# MBC3_1-4.net
KiCad netlist of a schematic drawn in EAGLE
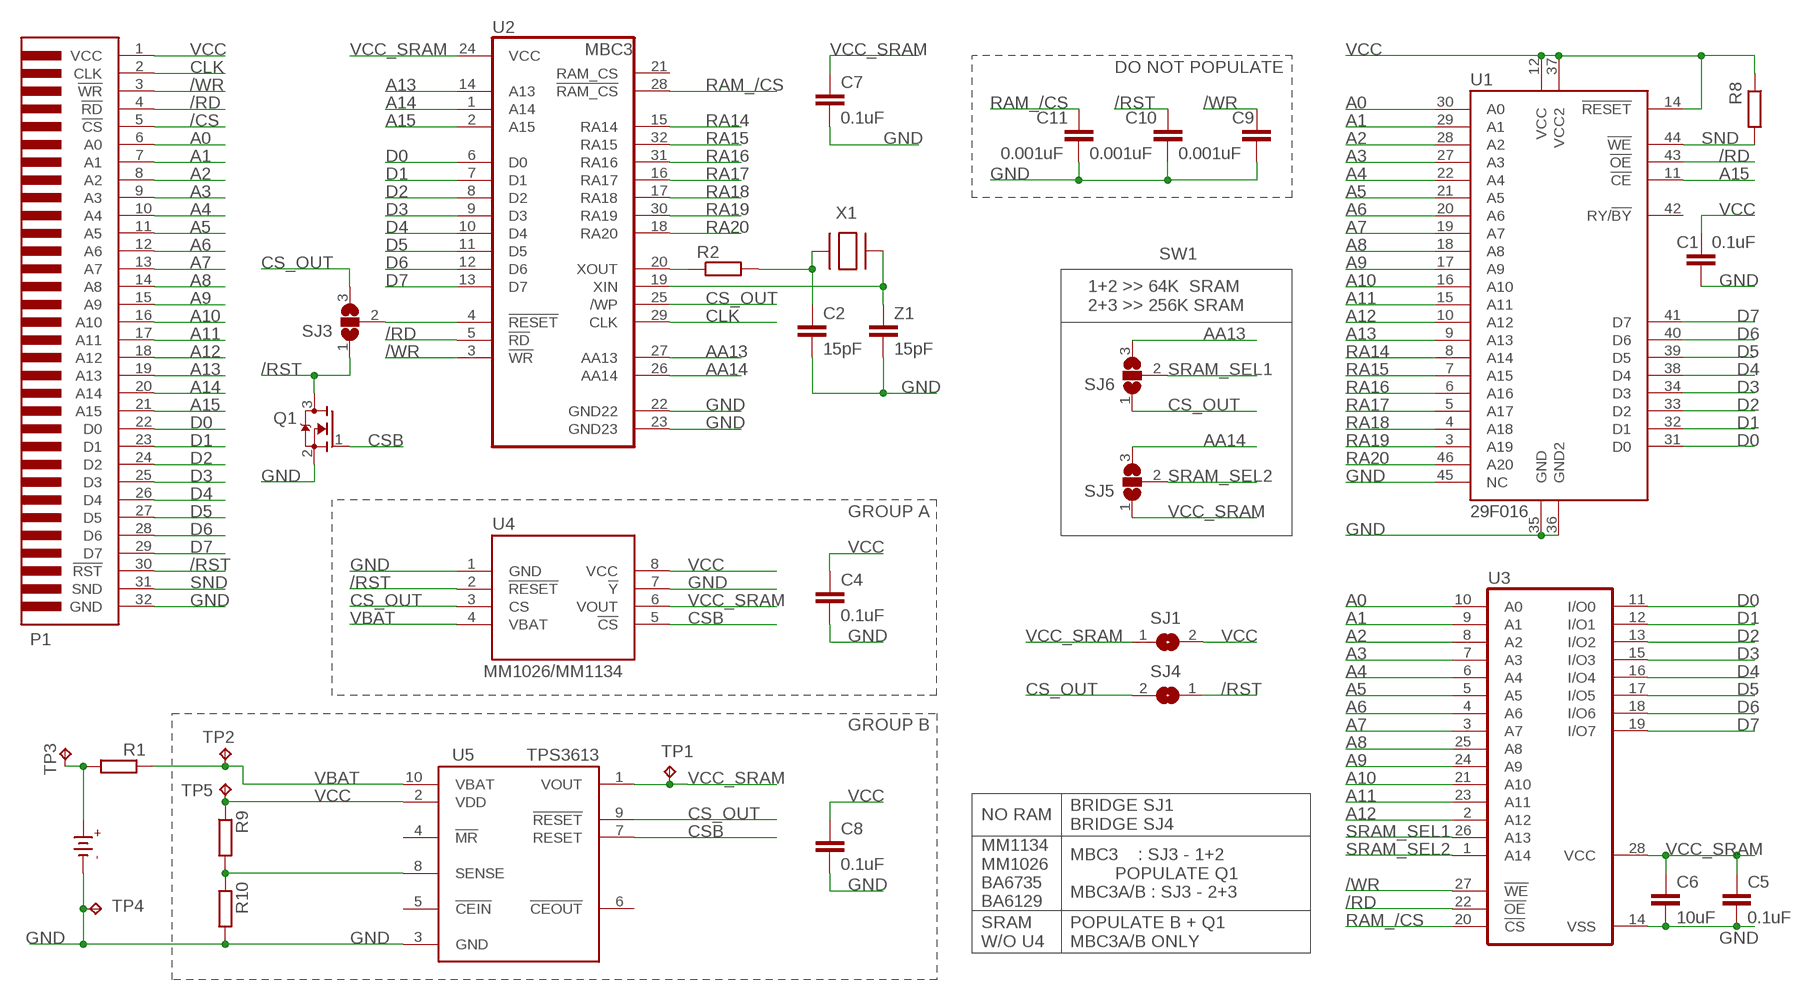
[diagram p0: schematic, sheet 1]

(export (version "E")
  (design (tool "Eeschema 10.0.6"))
  (components
    (comp (ref "B1")
      (value "CR2025")
      (footprint "eagle-import:CR2025")
      (libsource (lib "eagle-import") (part "CR2025"))
    )
    (comp (ref "C1")
      (value "0.1uF")
      (footprint "eagle-import:C0603")
      (libsource (lib "eagle-import") (part "C-EUC0603"))
    )
    (comp (ref "C2")
      (value "15pF")
      (footprint "eagle-import:C0603")
      (libsource (lib "eagle-import") (part "C-EUC0603"))
    )
    (comp (ref "C4")
      (value "0.1uF")
      (footprint "eagle-import:C0603")
      (libsource (lib "eagle-import") (part "C-EUC0603"))
    )
    (comp (ref "C5")
      (value "0.1uF")
      (footprint "eagle-import:C0603")
      (libsource (lib "eagle-import") (part "C-EUC0603"))
    )
    (comp (ref "C6")
      (value "10uF")
      (footprint "eagle-import:C0603")
      (libsource (lib "eagle-import") (part "C-EUC0603"))
    )
    (comp (ref "C7")
      (value "0.1uF")
      (footprint "eagle-import:C0603")
      (libsource (lib "eagle-import") (part "C-EUC0603"))
    )
    (comp (ref "C8")
      (value "0.1uF")
      (footprint "eagle-import:C0603")
      (libsource (lib "eagle-import") (part "C-EUC0603"))
    )
    (comp (ref "C9")
      (value "0.001uF")
      (footprint "eagle-import:C0603")
      (libsource (lib "eagle-import") (part "C-EUC0603"))
    )
    (comp (ref "C10")
      (value "0.001uF")
      (footprint "eagle-import:C0603")
      (libsource (lib "eagle-import") (part "C-EUC0603"))
    )
    (comp (ref "C11")
      (value "0.001uF")
      (footprint "eagle-import:C0603")
      (libsource (lib "eagle-import") (part "C-EUC0603"))
    )
    (comp (ref "P1")
      (value "GBC_CARTTAB")
      (footprint "eagle-import:GBC_CART_TABBED")
      (libsource (lib "eagle-import") (part "GBC_CARTTAB"))
    )
    (comp (ref "Q1")
      (value "2N7002")
      (footprint "eagle-import:SOT23")
      (libsource (lib "eagle-import") (part "MOSFET-NREFLOW"))
    )
    (comp (ref "R1")
      (value "RR0603")
      (footprint "eagle-import:R0603")
      (libsource (lib "eagle-import") (part "RR0603"))
    )
    (comp (ref "R2")
      (value "RR0603")
      (footprint "eagle-import:R0603")
      (libsource (lib "eagle-import") (part "RR0603"))
    )
    (comp (ref "R8")
      (value "RR0603")
      (footprint "eagle-import:R0603")
      (libsource (lib "eagle-import") (part "RR0603"))
    )
    (comp (ref "R9")
      (value "RR0603")
      (footprint "eagle-import:R0603")
      (libsource (lib "eagle-import") (part "RR0603"))
    )
    (comp (ref "R10")
      (value "RR0603")
      (footprint "eagle-import:R0603")
      (libsource (lib "eagle-import") (part "RR0603"))
    )
    (comp (ref "SJ1") (value "SJ") (footprint "eagle-import:SJ") (libsource (lib "eagle-import") (part "SJ")))
    (comp (ref "SJ3")
      (value "SJ2W")
      (footprint "eagle-import:SJ_2")
      (libsource (lib "eagle-import") (part "SJ2W"))
    )
    (comp (ref "SJ4") (value "SJ") (footprint "eagle-import:SJ") (libsource (lib "eagle-import") (part "SJ")))
    (comp (ref "SJ5")
      (value "SJ2W")
      (footprint "eagle-import:SJ_2")
      (libsource (lib "eagle-import") (part "SJ2W"))
    )
    (comp (ref "SJ6")
      (value "SJ2W")
      (footprint "eagle-import:SJ_2")
      (libsource (lib "eagle-import") (part "SJ2W"))
    )
    (comp (ref "TP1")
      (value "TPB1,27")
      (footprint "eagle-import:B1,27")
      (libsource (lib "eagle-import") (part "TPB1,27"))
    )
    (comp (ref "TP2")
      (value "TPB1,27")
      (footprint "eagle-import:B1,27")
      (libsource (lib "eagle-import") (part "TPB1,27"))
    )
    (comp (ref "TP3")
      (value "TPB1,27")
      (footprint "eagle-import:B1,27")
      (libsource (lib "eagle-import") (part "TPB1,27"))
    )
    (comp (ref "TP4")
      (value "TPB1,27")
      (footprint "eagle-import:B1,27")
      (libsource (lib "eagle-import") (part "TPB1,27"))
    )
    (comp (ref "TP5")
      (value "TPB1,27")
      (footprint "eagle-import:B1,27")
      (libsource (lib "eagle-import") (part "TPB1,27"))
    )
    (comp (ref "U1")
      (value "29F016")
      (footprint "eagle-import:TSOP-48")
      (libsource (lib "eagle-import") (part "29F016"))
    )
    (comp (ref "U2")
      (value "MBC3")
      (footprint "eagle-import:QFP-32")
      (libsource (lib "eagle-import") (part "MBC3"))
    )
    (comp (ref "U3")
      (value "62256_SRAM")
      (footprint "eagle-import:SOP-28L")
      (fields (field (name "MPN") "CY62256VNLL-70SNXI"))
      (libsource (lib "eagle-import") (part "62256_SRAM"))
    )
    (comp (ref "U4")
      (value "MM1134")
      (footprint "eagle-import:SOIC-8")
      (libsource (lib "eagle-import") (part "MM1134"))
    )
    (comp (ref "U5")
      (value "TPS3613")
      (footprint "eagle-import:MSOP-10")
      (libsource (lib "eagle-import") (part "TPS3613"))
    )
    (comp (ref "X1")
      (value "XTAL-3.2X1.5")
      (footprint "eagle-import:XTAL3215")
      (libsource (lib "eagle-import") (part "XTAL-3.2X1.5"))
    )
    (comp (ref "Z1")
      (value "15pF")
      (footprint "eagle-import:C0603")
      (libsource (lib "eagle-import") (part "C-EUC0603"))
    )
  )
  (nets
    (net (code "1") (name "/A0") (class "Default")
      (node (ref "P1") (pin "6") (pinfunction "A0_6") (pintype "output"))
      (node (ref "U1") (pin "30") (pinfunction "A0_30") (pintype "input"))
      (node (ref "U3") (pin "10") (pinfunction "A0_10") (pintype "input"))
    )
    (net (code "2") (name "/A1") (class "Default")
      (node (ref "P1") (pin "7") (pinfunction "A1_7") (pintype "output"))
      (node (ref "U1") (pin "29") (pinfunction "A1_29") (pintype "input"))
      (node (ref "U3") (pin "9") (pinfunction "A1_9") (pintype "input"))
    )
    (net (code "3") (name "/A2") (class "Default")
      (node (ref "P1") (pin "8") (pinfunction "A2_8") (pintype "output"))
      (node (ref "U1") (pin "28") (pinfunction "A2_28") (pintype "input"))
      (node (ref "U3") (pin "8") (pinfunction "A2_8") (pintype "input"))
    )
    (net (code "4") (name "/A3") (class "Default")
      (node (ref "P1") (pin "9") (pinfunction "A3_9") (pintype "output"))
      (node (ref "U1") (pin "27") (pinfunction "A3_27") (pintype "input"))
      (node (ref "U3") (pin "7") (pinfunction "A3_7") (pintype "input"))
    )
    (net (code "5") (name "/A4") (class "Default")
      (node (ref "P1") (pin "10") (pinfunction "A4_10") (pintype "output"))
      (node (ref "U1") (pin "22") (pinfunction "A4_22") (pintype "input"))
      (node (ref "U3") (pin "6") (pinfunction "A4_6") (pintype "input"))
    )
    (net (code "6") (name "/A5") (class "Default")
      (node (ref "P1") (pin "11") (pinfunction "A5_11") (pintype "output"))
      (node (ref "U1") (pin "21") (pinfunction "A5_21") (pintype "input"))
      (node (ref "U3") (pin "5") (pinfunction "A5_5") (pintype "input"))
    )
    (net (code "7") (name "/A6") (class "Default")
      (node (ref "P1") (pin "12") (pinfunction "A6_12") (pintype "output"))
      (node (ref "U1") (pin "20") (pinfunction "A6_20") (pintype "input"))
      (node (ref "U3") (pin "4") (pinfunction "A6_4") (pintype "input"))
    )
    (net (code "8") (name "/A7") (class "Default")
      (node (ref "P1") (pin "13") (pinfunction "A7_13") (pintype "output"))
      (node (ref "U1") (pin "19") (pinfunction "A7_19") (pintype "input"))
      (node (ref "U3") (pin "3") (pinfunction "A7_3") (pintype "input"))
    )
    (net (code "9") (name "/A8") (class "Default")
      (node (ref "P1") (pin "14") (pinfunction "A8_14") (pintype "output"))
      (node (ref "U1") (pin "18") (pinfunction "A8_18") (pintype "input"))
      (node (ref "U3") (pin "25") (pinfunction "A8_25") (pintype "input"))
    )
    (net (code "10") (name "/A9") (class "Default")
      (node (ref "P1") (pin "15") (pinfunction "A9_15") (pintype "output"))
      (node (ref "U1") (pin "17") (pinfunction "A9_17") (pintype "input"))
      (node (ref "U3") (pin "24") (pinfunction "A9_24") (pintype "input"))
    )
    (net (code "11") (name "/A10") (class "Default")
      (node (ref "P1") (pin "16") (pinfunction "A10_16") (pintype "output"))
      (node (ref "U1") (pin "16") (pinfunction "A10_16") (pintype "input"))
      (node (ref "U3") (pin "21") (pinfunction "A10_21") (pintype "input"))
    )
    (net (code "12") (name "/A11") (class "Default")
      (node (ref "P1") (pin "17") (pinfunction "A11_17") (pintype "output"))
      (node (ref "U1") (pin "15") (pinfunction "A11_15") (pintype "input"))
      (node (ref "U3") (pin "23") (pinfunction "A11_23") (pintype "input"))
    )
    (net (code "13") (name "/A12") (class "Default")
      (node (ref "P1") (pin "18") (pinfunction "A12_18") (pintype "output"))
      (node (ref "U1") (pin "10") (pinfunction "A12_10") (pintype "input"))
      (node (ref "U3") (pin "2") (pinfunction "A12_2") (pintype "input"))
    )
    (net (code "14") (name "/A13") (class "Default")
      (node (ref "P1") (pin "19") (pinfunction "A13_19") (pintype "output"))
      (node (ref "U1") (pin "9") (pinfunction "A13_9") (pintype "input"))
      (node (ref "U2") (pin "14") (pinfunction "A13_14") (pintype "input"))
    )
    (net (code "15") (name "/A14") (class "Default")
      (node (ref "P1") (pin "20") (pinfunction "A14_20") (pintype "output"))
      (node (ref "U2") (pin "1") (pinfunction "A14_1") (pintype "input"))
    )
    (net (code "16") (name "/A15") (class "Default")
      (node (ref "P1") (pin "21") (pinfunction "A15_21") (pintype "output"))
      (node (ref "U1") (pin "11") (pinfunction "~{CE}_11") (pintype "input"))
      (node (ref "U2") (pin "2") (pinfunction "A15_2") (pintype "input"))
    )
    (net (code "17") (name "/AA13") (class "Default")
      (node (ref "SJ6") (pin "3") (pinfunction "3_3") (pintype "passive"))
      (node (ref "U2") (pin "27") (pinfunction "AA13_27") (pintype "output"))
    )
    (net (code "18") (name "/AA14") (class "Default")
      (node (ref "SJ5") (pin "3") (pinfunction "3_3") (pintype "passive"))
      (node (ref "U2") (pin "26") (pinfunction "AA14_26") (pintype "output"))
    )
    (net (code "19") (name "/CLK") (class "Default")
      (node (ref "P1") (pin "2") (pinfunction "CLK_2") (pintype "output"))
      (node (ref "U2") (pin "29") (pinfunction "CLK_29") (pintype "output"))
    )
    (net (code "20") (name "/CSB") (class "Default")
      (node (ref "Q1") (pin "1") (pinfunction "G_1") (pintype "bidirectional"))
      (node (ref "U4") (pin "5") (pinfunction "~{CS}_5") (pintype "output"))
      (node (ref "U5") (pin "7") (pinfunction "RESET_7") (pintype "output"))
    )
    (net (code "21") (name "/CS_OUT") (class "Default")
      (node (ref "SJ3") (pin "3") (pinfunction "3_3") (pintype "passive"))
      (node (ref "SJ4") (pin "2") (pinfunction "2_2") (pintype "passive"))
      (node (ref "SJ6") (pin "1") (pinfunction "1_1") (pintype "passive"))
      (node (ref "U2") (pin "25") (pinfunction "/WP_25") (pintype "output"))
      (node (ref "U4") (pin "3") (pinfunction "CS_3") (pintype "output"))
      (node (ref "U5") (pin "9") (pinfunction "~{RESET}_9") (pintype "output"))
    )
    (net (code "22") (name "/D0") (class "Default")
      (node (ref "P1") (pin "22") (pinfunction "D0_22") (pintype "bidirectional"))
      (node (ref "U1") (pin "31") (pinfunction "D0_31") (pintype "bidirectional"))
      (node (ref "U2") (pin "6") (pinfunction "D0_6") (pintype "input"))
      (node (ref "U3") (pin "11") (pinfunction "I/O0_11") (pintype "bidirectional"))
    )
    (net (code "23") (name "/D1") (class "Default")
      (node (ref "P1") (pin "23") (pinfunction "D1_23") (pintype "bidirectional"))
      (node (ref "U1") (pin "32") (pinfunction "D1_32") (pintype "bidirectional"))
      (node (ref "U2") (pin "7") (pinfunction "D1_7") (pintype "input"))
      (node (ref "U3") (pin "12") (pinfunction "I/O1_12") (pintype "bidirectional"))
    )
    (net (code "24") (name "/D2") (class "Default")
      (node (ref "P1") (pin "24") (pinfunction "D2_24") (pintype "bidirectional"))
      (node (ref "U1") (pin "33") (pinfunction "D2_33") (pintype "bidirectional"))
      (node (ref "U2") (pin "8") (pinfunction "D2_8") (pintype "input"))
      (node (ref "U3") (pin "13") (pinfunction "I/O2_13") (pintype "bidirectional"))
    )
    (net (code "25") (name "/D3") (class "Default")
      (node (ref "P1") (pin "25") (pinfunction "D3_25") (pintype "bidirectional"))
      (node (ref "U1") (pin "34") (pinfunction "D3_34") (pintype "bidirectional"))
      (node (ref "U2") (pin "9") (pinfunction "D3_9") (pintype "input"))
      (node (ref "U3") (pin "15") (pinfunction "I/O3_15") (pintype "bidirectional"))
    )
    (net (code "26") (name "/D4") (class "Default")
      (node (ref "P1") (pin "26") (pinfunction "D4_26") (pintype "bidirectional"))
      (node (ref "U1") (pin "38") (pinfunction "D4_38") (pintype "bidirectional"))
      (node (ref "U2") (pin "10") (pinfunction "D4_10") (pintype "input"))
      (node (ref "U3") (pin "16") (pinfunction "I/O4_16") (pintype "bidirectional"))
    )
    (net (code "27") (name "/D5") (class "Default")
      (node (ref "P1") (pin "27") (pinfunction "D5_27") (pintype "bidirectional"))
      (node (ref "U1") (pin "39") (pinfunction "D5_39") (pintype "bidirectional"))
      (node (ref "U2") (pin "11") (pinfunction "D5_11") (pintype "input"))
      (node (ref "U3") (pin "17") (pinfunction "I/O5_17") (pintype "bidirectional"))
    )
    (net (code "28") (name "/D6") (class "Default")
      (node (ref "P1") (pin "28") (pinfunction "D6_28") (pintype "bidirectional"))
      (node (ref "U1") (pin "40") (pinfunction "D6_40") (pintype "bidirectional"))
      (node (ref "U2") (pin "12") (pinfunction "D6_12") (pintype "input"))
      (node (ref "U3") (pin "18") (pinfunction "I/O6_18") (pintype "bidirectional"))
    )
    (net (code "29") (name "/D7") (class "Default")
      (node (ref "P1") (pin "29") (pinfunction "D7_29") (pintype "bidirectional"))
      (node (ref "U1") (pin "41") (pinfunction "D7_41") (pintype "bidirectional"))
      (node (ref "U2") (pin "13") (pinfunction "D7_13") (pintype "input"))
      (node (ref "U3") (pin "19") (pinfunction "I/O7_19") (pintype "bidirectional"))
    )
    (net (code "30") (name "/GND") (class "Default")
      (node (ref "B1") (pin "-") (pinfunction "-_-") (pintype "power_in"))
      (node (ref "C1") (pin "2") (pinfunction "2_2") (pintype "passive"))
      (node (ref "C10") (pin "2") (pinfunction "2_2") (pintype "passive"))
      (node (ref "C11") (pin "2") (pinfunction "2_2") (pintype "passive"))
      (node (ref "C2") (pin "2") (pinfunction "2_2") (pintype "passive"))
      (node (ref "C4") (pin "2") (pinfunction "2_2") (pintype "passive"))
      (node (ref "C5") (pin "2") (pinfunction "2_2") (pintype "passive"))
      (node (ref "C6") (pin "2") (pinfunction "2_2") (pintype "passive"))
      (node (ref "C7") (pin "2") (pinfunction "2_2") (pintype "passive"))
      (node (ref "C8") (pin "2") (pinfunction "2_2") (pintype "passive"))
      (node (ref "C9") (pin "2") (pinfunction "2_2") (pintype "passive"))
      (node (ref "P1") (pin "32") (pinfunction "GND_32") (pintype "power_in"))
      (node (ref "Q1") (pin "2") (pinfunction "S_2") (pintype "bidirectional"))
      (node (ref "R10") (pin "2") (pinfunction "2_2") (pintype "passive"))
      (node (ref "TP4") (pin "TP") (pinfunction "TP_TP") (pintype "input"))
      (node (ref "U1") (pin "35") (pinfunction "GND_35") (pintype "power_in"))
      (node (ref "U1") (pin "36") (pinfunction "GND2_36") (pintype "power_in"))
      (node (ref "U1") (pin "45") (pinfunction "NC_45") (pintype "input"))
      (node (ref "U2") (pin "22") (pinfunction "GND22_22") (pintype "power_in"))
      (node (ref "U2") (pin "23") (pinfunction "GND23_23") (pintype "power_in"))
      (node (ref "U3") (pin "14") (pinfunction "VSS_14") (pintype "power_in"))
      (node (ref "U4") (pin "1") (pinfunction "GND_1") (pintype "power_in"))
      (node (ref "U4") (pin "7") (pinfunction "~{Y}_7") (pintype "input"))
      (node (ref "U5") (pin "3") (pinfunction "GND_3") (pintype "power_in"))
      (node (ref "Z1") (pin "2") (pinfunction "2_2") (pintype "passive"))
    )
    (net (code "31") (name "/RA14") (class "Default")
      (node (ref "U1") (pin "8") (pinfunction "A14_8") (pintype "input"))
      (node (ref "U2") (pin "15") (pinfunction "RA14_15") (pintype "output"))
    )
    (net (code "32") (name "/RA15") (class "Default")
      (node (ref "U1") (pin "7") (pinfunction "A15_7") (pintype "input"))
      (node (ref "U2") (pin "32") (pinfunction "RA15_32") (pintype "output"))
    )
    (net (code "33") (name "/RA16") (class "Default")
      (node (ref "U1") (pin "6") (pinfunction "A16_6") (pintype "input"))
      (node (ref "U2") (pin "31") (pinfunction "RA16_31") (pintype "output"))
    )
    (net (code "34") (name "/RA17") (class "Default")
      (node (ref "U1") (pin "5") (pinfunction "A17_5") (pintype "input"))
      (node (ref "U2") (pin "16") (pinfunction "RA17_16") (pintype "output"))
    )
    (net (code "35") (name "/RA18") (class "Default")
      (node (ref "U1") (pin "4") (pinfunction "A18_4") (pintype "input"))
      (node (ref "U2") (pin "17") (pinfunction "RA18_17") (pintype "output"))
    )
    (net (code "36") (name "/RA19") (class "Default")
      (node (ref "U1") (pin "3") (pinfunction "A19_3") (pintype "input"))
      (node (ref "U2") (pin "30") (pinfunction "RA19_30") (pintype "output"))
    )
    (net (code "37") (name "/RA20") (class "Default")
      (node (ref "U1") (pin "46") (pinfunction "A20_46") (pintype "input"))
      (node (ref "U2") (pin "18") (pinfunction "RA20_18") (pintype "output"))
    )
    (net (code "38") (name "/RAM_{slash}CS") (class "Default")
      (node (ref "C11") (pin "1") (pinfunction "1_1") (pintype "passive"))
      (node (ref "U2") (pin "28") (pinfunction "~{RAM_CS}_28") (pintype "output"))
      (node (ref "U3") (pin "20") (pinfunction "~{CS}_20") (pintype "input"))
    )
    (net (code "39") (name "/SND") (class "Default")
      (node (ref "P1") (pin "31") (pinfunction "SND_31") (pintype "bidirectional"))
      (node (ref "R8") (pin "2") (pinfunction "2_2") (pintype "passive"))
      (node (ref "U1") (pin "44") (pinfunction "~{WE}_44") (pintype "input"))
    )
    (net (code "40") (name "/SRAM_SEL1") (class "Default")
      (node (ref "SJ6") (pin "2") (pinfunction "2_2") (pintype "passive"))
      (node (ref "U3") (pin "26") (pinfunction "A13_26") (pintype "input"))
    )
    (net (code "41") (name "/SRAM_SEL2") (class "Default")
      (node (ref "SJ5") (pin "2") (pinfunction "2_2") (pintype "passive"))
      (node (ref "U3") (pin "1") (pinfunction "A14_1") (pintype "input"))
    )
    (net (code "42") (name "/VBAT") (class "Default")
      (node (ref "R1") (pin "1") (pinfunction "1_1") (pintype "passive"))
      (node (ref "TP2") (pin "TP") (pinfunction "TP_TP") (pintype "input"))
      (node (ref "U4") (pin "4") (pinfunction "VBAT_4") (pintype "power_in"))
      (node (ref "U5") (pin "10") (pinfunction "VBAT_10") (pintype "power_in"))
    )
    (net (code "43") (name "/VCC") (class "Default")
      (node (ref "C1") (pin "1") (pinfunction "1_1") (pintype "passive"))
      (node (ref "C4") (pin "1") (pinfunction "1_1") (pintype "passive"))
      (node (ref "C8") (pin "1") (pinfunction "1_1") (pintype "passive"))
      (node (ref "P1") (pin "1") (pinfunction "VCC_1") (pintype "power_in"))
      (node (ref "R8") (pin "1") (pinfunction "1_1") (pintype "passive"))
      (node (ref "R9") (pin "1") (pinfunction "1_1") (pintype "passive"))
      (node (ref "SJ1") (pin "2") (pinfunction "2_2") (pintype "passive"))
      (node (ref "TP5") (pin "TP") (pinfunction "TP_TP") (pintype "input"))
      (node (ref "U1") (pin "12") (pinfunction "VCC_12") (pintype "power_in"))
      (node (ref "U1") (pin "14") (pinfunction "~{RESET}_14") (pintype "input"))
      (node (ref "U1") (pin "37") (pinfunction "VCC2_37") (pintype "power_in"))
      (node (ref "U4") (pin "8") (pinfunction "VCC_8") (pintype "power_in"))
      (node (ref "U5") (pin "2") (pinfunction "VDD_2") (pintype "power_in"))
    )
    (net (code "44") (name "/VCC_SRAM") (class "Default")
      (node (ref "C5") (pin "1") (pinfunction "1_1") (pintype "passive"))
      (node (ref "C6") (pin "1") (pinfunction "1_1") (pintype "passive"))
      (node (ref "C7") (pin "1") (pinfunction "1_1") (pintype "passive"))
      (node (ref "SJ1") (pin "1") (pinfunction "1_1") (pintype "passive"))
      (node (ref "SJ5") (pin "1") (pinfunction "1_1") (pintype "passive"))
      (node (ref "TP1") (pin "TP") (pinfunction "TP_TP") (pintype "input"))
      (node (ref "U2") (pin "24") (pinfunction "VCC_24") (pintype "power_in"))
      (node (ref "U3") (pin "28") (pinfunction "VCC_28") (pintype "power_in"))
      (node (ref "U4") (pin "6") (pinfunction "VOUT_6") (pintype "power_in"))
      (node (ref "U5") (pin "1") (pinfunction "VOUT_1") (pintype "power_in"))
    )
    (net (code "45") (name "/{slash}CS") (class "Default")
      (node (ref "P1") (pin "5") (pinfunction "~{CS}_5") (pintype "output"))
    )
    (net (code "46") (name "/{slash}RD") (class "Default")
      (node (ref "P1") (pin "4") (pinfunction "~{RD}_4") (pintype "output"))
      (node (ref "U1") (pin "43") (pinfunction "~{OE}_43") (pintype "input"))
      (node (ref "U2") (pin "5") (pinfunction "~{RD}_5") (pintype "input"))
      (node (ref "U3") (pin "22") (pinfunction "~{OE}_22") (pintype "input"))
    )
    (net (code "47") (name "/{slash}RST") (class "Default")
      (node (ref "C10") (pin "1") (pinfunction "1_1") (pintype "passive"))
      (node (ref "P1") (pin "30") (pinfunction "~{RST}_30") (pintype "bidirectional"))
      (node (ref "Q1") (pin "3") (pinfunction "D_3") (pintype "bidirectional"))
      (node (ref "SJ3") (pin "1") (pinfunction "1_1") (pintype "passive"))
      (node (ref "SJ4") (pin "1") (pinfunction "1_1") (pintype "passive"))
      (node (ref "U4") (pin "2") (pinfunction "~{RESET}_2") (pintype "input"))
    )
    (net (code "48") (name "/{slash}WR") (class "Default")
      (node (ref "C9") (pin "1") (pinfunction "1_1") (pintype "passive"))
      (node (ref "P1") (pin "3") (pinfunction "~{WR}_3") (pintype "output"))
      (node (ref "U2") (pin "3") (pinfunction "~{WR}_3") (pintype "input"))
      (node (ref "U3") (pin "27") (pinfunction "~{WE}_27") (pintype "input"))
    )
    (net (code "49") (name "Net-(B1-Pad+)") (class "Default")
      (node (ref "B1") (pin "+") (pinfunction "+_+") (pintype "power_in"))
      (node (ref "R1") (pin "2") (pinfunction "2_2") (pintype "passive"))
      (node (ref "TP3") (pin "TP") (pinfunction "TP_TP") (pintype "input"))
    )
    (net (code "50") (name "Net-(C2-Pad1)") (class "Default")
      (node (ref "C2") (pin "1") (pinfunction "1_1") (pintype "passive"))
      (node (ref "R2") (pin "2") (pinfunction "2_2") (pintype "passive"))
      (node (ref "X1") (pin "P$2") (pinfunction "P$2_P$2") (pintype "bidirectional"))
    )
    (net (code "51") (name "Net-(U2-XIN)") (class "Default")
      (node (ref "U2") (pin "19") (pinfunction "XIN_19") (pintype "input"))
      (node (ref "X1") (pin "P$1") (pinfunction "P$1_P$1") (pintype "bidirectional"))
      (node (ref "Z1") (pin "1") (pinfunction "1_1") (pintype "passive"))
    )
    (net (code "52") (name "Net-(U2-XOUT)") (class "Default")
      (node (ref "R2") (pin "1") (pinfunction "1_1") (pintype "passive"))
      (node (ref "U2") (pin "20") (pinfunction "XOUT_20") (pintype "output"))
    )
    (net (code "53") (name "Net-(U2-~{RESET})") (class "Default")
      (node (ref "SJ3") (pin "2") (pinfunction "2_2") (pintype "passive"))
      (node (ref "U2") (pin "4") (pinfunction "~{RESET}_4") (pintype "input"))
    )
    (net (code "54") (name "Net-(U5-SENSE)") (class "Default")
      (node (ref "R10") (pin "1") (pinfunction "1_1") (pintype "passive"))
      (node (ref "R9") (pin "2") (pinfunction "2_2") (pintype "passive"))
      (node (ref "U5") (pin "8") (pinfunction "SENSE_8") (pintype "input"))
    )
    (net (code "55") (name "unconnected-(U1-RY{slash}~{BY}-Pad42)") (class "Default")
      (node (ref "U1") (pin "42") (pinfunction "RY/~{BY}_42") (pintype "output"))
    )
    (net (code "56") (name "unconnected-(U2-RAM_CS-Pad21)") (class "Default")
      (node (ref "U2") (pin "21") (pinfunction "RAM_CS_21") (pintype "output"))
    )
    (net (code "57") (name "unconnected-(U5-~{CEIN}-Pad5)") (class "Default")
      (node (ref "U5") (pin "5") (pinfunction "~{CEIN}_5") (pintype "input"))
    )
    (net (code "58") (name "unconnected-(U5-~{CEOUT}-Pad6)") (class "Default")
      (node (ref "U5") (pin "6") (pinfunction "~{CEOUT}_6") (pintype "output"))
    )
    (net (code "59") (name "unconnected-(U5-~{MR}-Pad4)") (class "Default")
      (node (ref "U5") (pin "4") (pinfunction "~{MR}_4") (pintype "input"))
    )
  )
)
